# Final_3.net
KiCad netlist of a schematic drawn in EAGLE
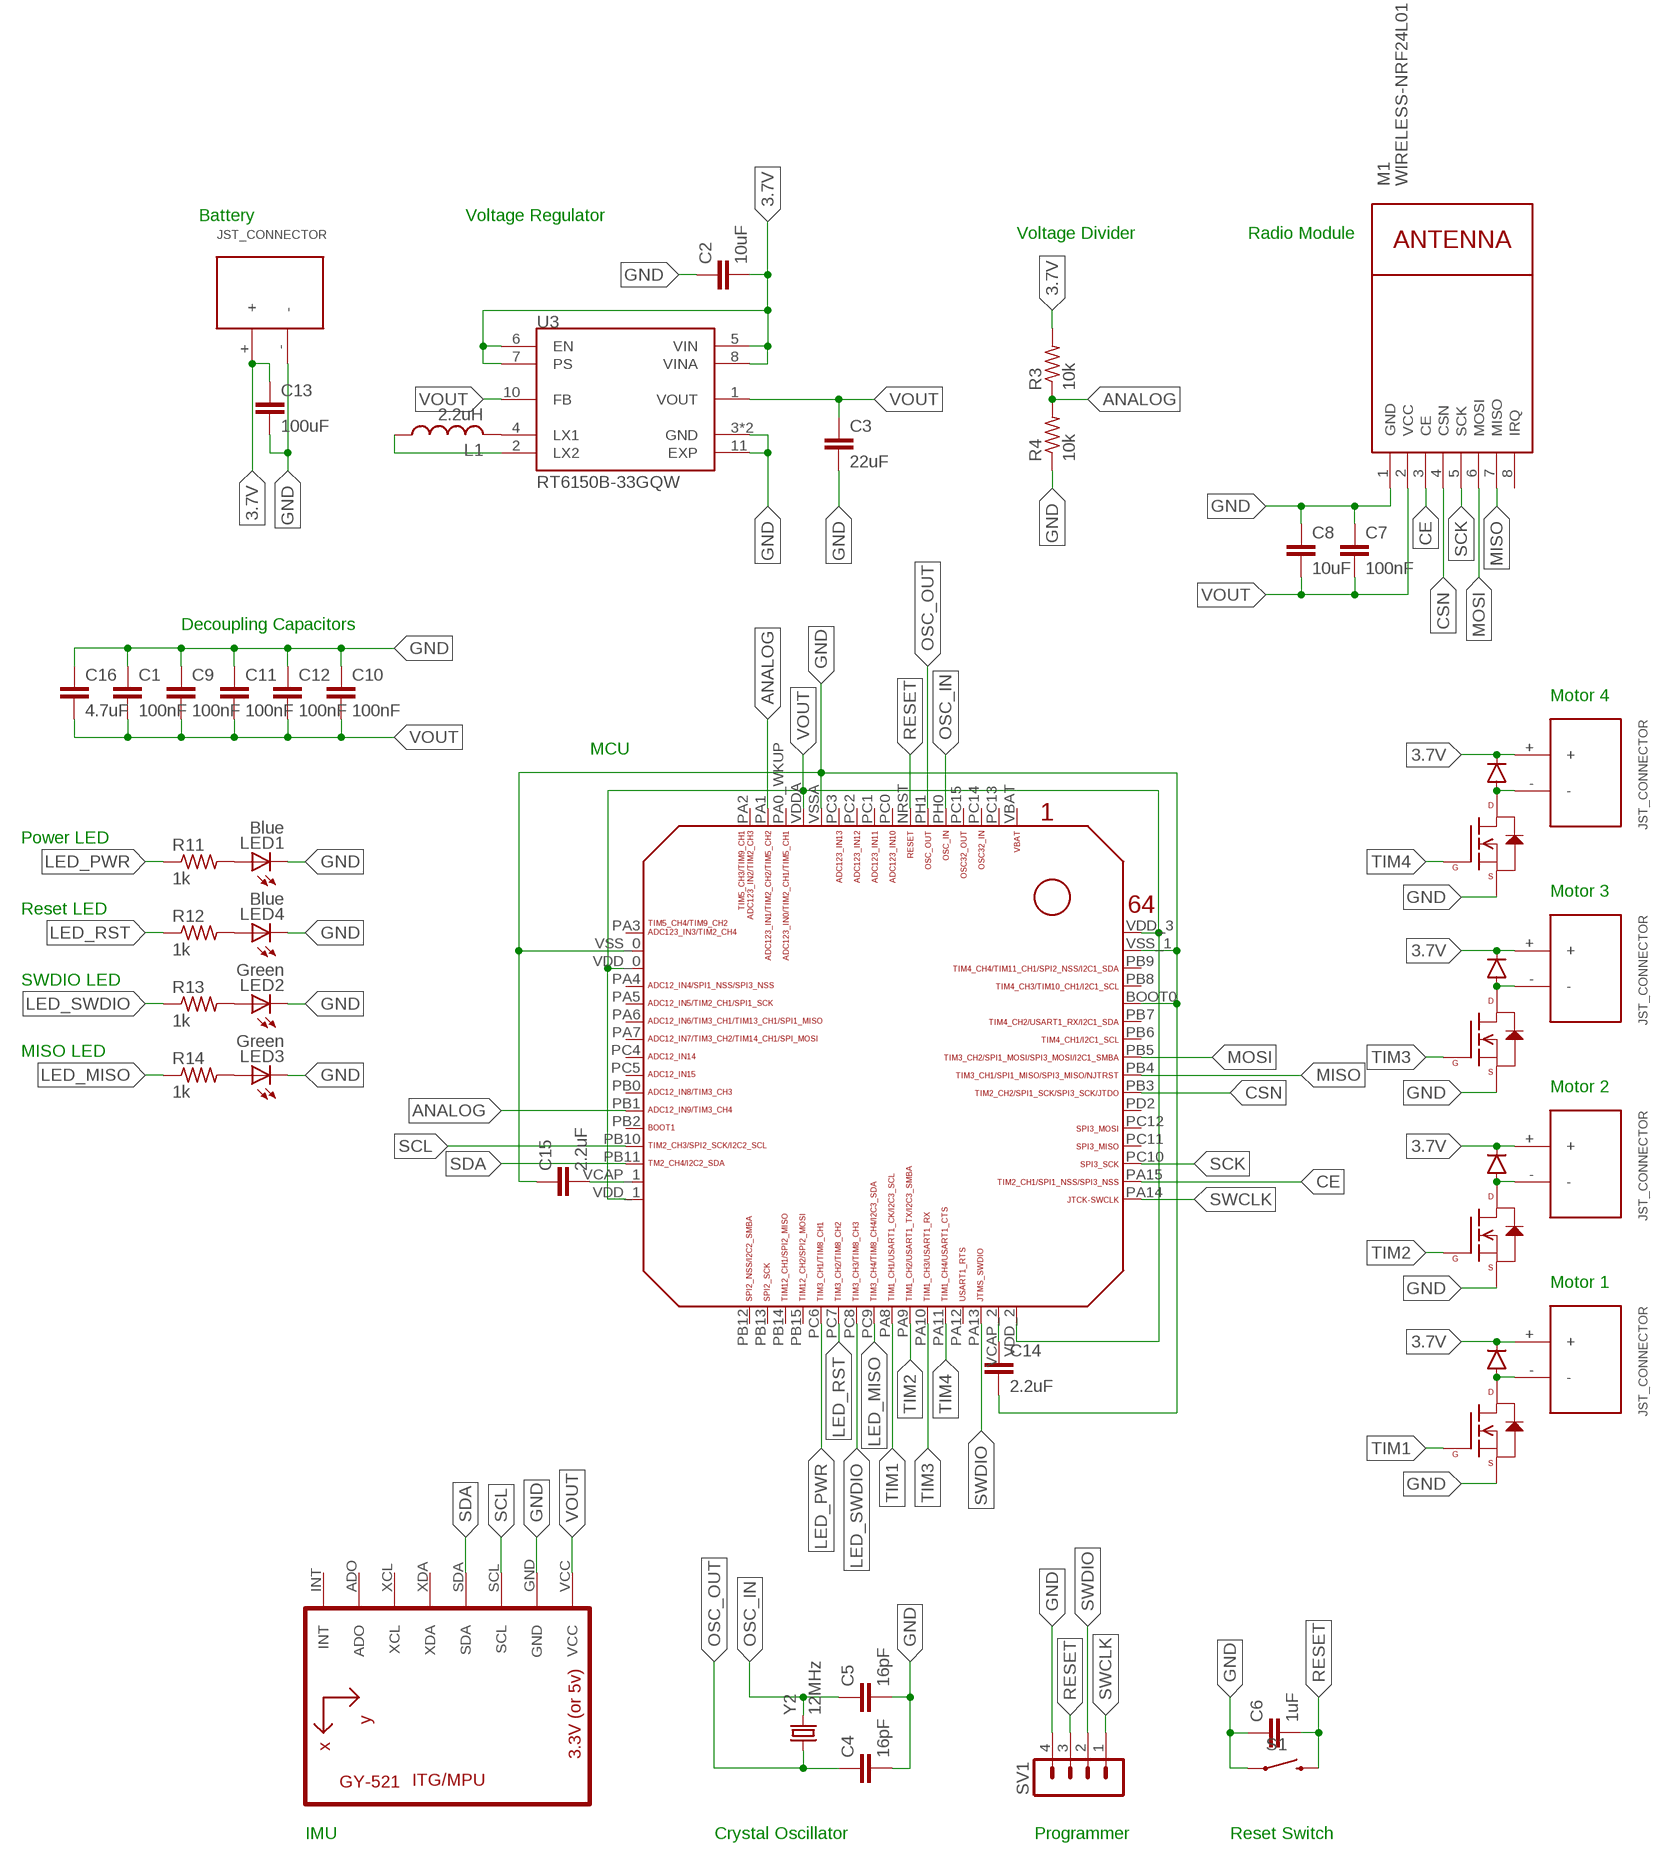
[diagram p0: schematic, sheet 1]

(export (version "E")
  (design (tool "Eeschema 10.0.6"))
  (components
    (comp (ref "C1")
      (value "100nF")
      (footprint "eagle-import:C0603")
      (libsource (lib "eagle-import") (part "rcl_334_C-EUC0603"))
    )
    (comp (ref "C2")
      (value "10uF")
      (footprint "eagle-import:C0603")
      (libsource (lib "eagle-import") (part "rcl_334_C-EUC0603"))
    )
    (comp (ref "C3")
      (value "22uF")
      (footprint "eagle-import:C0603")
      (libsource (lib "eagle-import") (part "rcl_334_C-EUC0603"))
    )
    (comp (ref "C4")
      (value "16pF")
      (footprint "eagle-import:C0603")
      (libsource (lib "eagle-import") (part "rcl_334_C-EUC0603"))
    )
    (comp (ref "C5")
      (value "16pF")
      (footprint "eagle-import:C0603")
      (libsource (lib "eagle-import") (part "rcl_334_C-EUC0603"))
    )
    (comp (ref "C6")
      (value "1uF")
      (footprint "eagle-import:C0603")
      (libsource (lib "eagle-import") (part "rcl_334_C-EUC0603"))
    )
    (comp (ref "C7")
      (value "100nF")
      (footprint "eagle-import:C0603")
      (libsource (lib "eagle-import") (part "rcl_334_C-EUC0603"))
    )
    (comp (ref "C8")
      (value "10uF")
      (footprint "eagle-import:C0603")
      (libsource (lib "eagle-import") (part "rcl_334_C-EUC0603"))
    )
    (comp (ref "C9")
      (value "100nF")
      (footprint "eagle-import:C0603")
      (libsource (lib "eagle-import") (part "rcl_334_C-EUC0603"))
    )
    (comp (ref "C10")
      (value "100nF")
      (footprint "eagle-import:C0603")
      (libsource (lib "eagle-import") (part "rcl_334_C-EUC0603"))
    )
    (comp (ref "C11")
      (value "100nF")
      (footprint "eagle-import:C0603")
      (libsource (lib "eagle-import") (part "rcl_334_C-EUC0603"))
    )
    (comp (ref "C12")
      (value "100nF")
      (footprint "eagle-import:C0603")
      (libsource (lib "eagle-import") (part "rcl_334_C-EUC0603"))
    )
    (comp (ref "C13")
      (value "100uF")
      (footprint "eagle-import:C1206")
      (libsource (lib "eagle-import") (part "rcl_334_C-EUC1206"))
    )
    (comp (ref "C14")
      (value "2.2uF")
      (footprint "eagle-import:C0603")
      (libsource (lib "eagle-import") (part "C-EUC0603"))
    )
    (comp (ref "C15")
      (value "2.2uF")
      (footprint "eagle-import:C0603")
      (libsource (lib "eagle-import") (part "C-EUC0603"))
    )
    (comp (ref "C16")
      (value "4.7uF")
      (footprint "eagle-import:C0603")
      (libsource (lib "eagle-import") (part "rcl_334_C-EUC0603"))
    )
    (comp (ref "L1")
      (value "2.2uH")
      (footprint "eagle-import:L0603")
      (libsource (lib "eagle-import") (part "L-USL0603"))
    )
    (comp (ref "LED1")
      (value "Blue")
      (footprint "eagle-import:CHIP-LED0603")
      (libsource (lib "eagle-import") (part "LEDCHIP-LED0603"))
    )
    (comp (ref "LED2")
      (value "Green")
      (footprint "eagle-import:CHIP-LED0603")
      (libsource (lib "eagle-import") (part "LEDCHIP-LED0603"))
    )
    (comp (ref "LED3")
      (value "Green")
      (footprint "eagle-import:CHIP-LED0603")
      (libsource (lib "eagle-import") (part "LEDCHIP-LED0603"))
    )
    (comp (ref "LED4")
      (value "Blue")
      (footprint "eagle-import:CHIP-LED0603")
      (libsource (lib "eagle-import") (part "LEDCHIP-LED0603"))
    )
    (comp (ref "M1")
      (value "WIRELESS-NRF24L01")
      (footprint "eagle-import:WIRELESS-NRF24L01")
      (libsource (lib "eagle-import") (part "WIRELESS-NRF24L01"))
    )
    (comp (ref "R3")
      (value "10k")
      (footprint "eagle-import:R0603")
      (libsource (lib "eagle-import") (part "R-US_R0603"))
    )
    (comp (ref "R4")
      (value "10k")
      (footprint "eagle-import:R0603")
      (libsource (lib "eagle-import") (part "R-US_R0603"))
    )
    (comp (ref "R11")
      (value "1k")
      (footprint "eagle-import:R0603")
      (libsource (lib "eagle-import") (part "R-US_R0603"))
    )
    (comp (ref "R12")
      (value "1k")
      (footprint "eagle-import:R0603")
      (libsource (lib "eagle-import") (part "R-US_R0603"))
    )
    (comp (ref "R13")
      (value "1k")
      (footprint "eagle-import:R0603")
      (libsource (lib "eagle-import") (part "R-US_R0603"))
    )
    (comp (ref "R14")
      (value "1k")
      (footprint "eagle-import:R0603")
      (libsource (lib "eagle-import") (part "R-US_R0603"))
    )
    (comp (ref "S1")
      (value "SWITCH-MOMENTARY-2SMD")
      (footprint "eagle-import:TACTILE-SWITCH-SMD")
      (libsource (lib "eagle-import") (part "SWITCH-MOMENTARY-2SMD"))
    )
    (comp (ref "SV1")
      (value "MA04-1")
      (footprint "eagle-import:MA04-1")
      (libsource (lib "eagle-import") (part "MA04-1"))
    )
    (comp (ref "U$1")
      (value "STM32F405/415_LQFP64")
      (footprint "eagle-import:STM32F405_415_LQFP64")
      (libsource (lib "eagle-import") (part "STM32F405/415_LQFP64"))
    )
    (comp (ref "U$2")
      (value "JST_CONNECTOR_FEMALE")
      (footprint "eagle-import:JST_CONNECTOR_FEMALE")
      (libsource (lib "eagle-import") (part "JST_CONNECTOR_FEMALE"))
    )
    (comp (ref "U$3")
      (value "JST_CONNECTOR_FEMALE")
      (footprint "eagle-import:JST_CONNECTOR_FEMALE")
      (libsource (lib "eagle-import") (part "JST_CONNECTOR_FEMALE"))
    )
    (comp (ref "U$4")
      (value "JST_CONNECTOR_FEMALE")
      (footprint "eagle-import:JST_CONNECTOR_FEMALE")
      (libsource (lib "eagle-import") (part "JST_CONNECTOR_FEMALE"))
    )
    (comp (ref "U$5")
      (value "JST_CONNECTOR_FEMALE")
      (footprint "eagle-import:JST_CONNECTOR_FEMALE")
      (libsource (lib "eagle-import") (part "JST_CONNECTOR_FEMALE"))
    )
    (comp (ref "U$6")
      (value "JST_CONNECTOR_FEMALE")
      (footprint "eagle-import:JST_CONNECTOR_FEMALE")
      (libsource (lib "eagle-import") (part "JST_CONNECTOR_FEMALE"))
    )
    (comp (ref "U$7")
      (value "N-CHANNEL-MOSFET-IRLML6244TRPBF")
      (footprint "eagle-import:SOT23-3")
      (libsource (lib "eagle-import") (part "N-CHANNEL-MOSFET-IRLML6244TRPBF"))
    )
    (comp (ref "U$8")
      (value "N-CHANNEL-MOSFET-IRLML6244TRPBF")
      (footprint "eagle-import:SOT23-3")
      (libsource (lib "eagle-import") (part "N-CHANNEL-MOSFET-IRLML6244TRPBF"))
    )
    (comp (ref "U$9")
      (value "N-CHANNEL-MOSFET-IRLML6244TRPBF")
      (footprint "eagle-import:SOT23-3")
      (libsource (lib "eagle-import") (part "N-CHANNEL-MOSFET-IRLML6244TRPBF"))
    )
    (comp (ref "U$10")
      (value "N-CHANNEL-MOSFET-IRLML6244TRPBF")
      (footprint "eagle-import:SOT23-3")
      (libsource (lib "eagle-import") (part "N-CHANNEL-MOSFET-IRLML6244TRPBF"))
    )
    (comp (ref "U$11")
      (value "DB2W40300L")
      (footprint "eagle-import:MINI2-F3-B")
      (libsource (lib "eagle-import") (part "DB2W40300L"))
    )
    (comp (ref "U$12")
      (value "DB2W40300L")
      (footprint "eagle-import:MINI2-F3-B")
      (libsource (lib "eagle-import") (part "DB2W40300L"))
    )
    (comp (ref "U$13")
      (value "DB2W40300L")
      (footprint "eagle-import:MINI2-F3-B")
      (libsource (lib "eagle-import") (part "DB2W40300L"))
    )
    (comp (ref "U$14")
      (value "DB2W40300L")
      (footprint "eagle-import:MINI2-F3-B")
      (libsource (lib "eagle-import") (part "DB2W40300L"))
    )
    (comp (ref "U2")
      (value "GY-521MPU6050")
      (footprint "eagle-import:GY-521")
      (libsource (lib "eagle-import") (part "GY-521MPU6050"))
    )
    (comp (ref "U3")
      (value "RT6150B-33GQW")
      (footprint "eagle-import:SON50P250X250X80-11N")
      (fields (field (name "DIGI-KEY_PART_NUMBER") "RT6150B-33GQWCT-ND") (field (name "MF") "Richtek USA"))
      (libsource (lib "eagle-import") (part "RT6150B-33GQW"))
    )
    (comp (ref "Y2")
      (value "12MHz")
      (footprint "eagle-import:HC49UP")
      (libsource (lib "eagle-import") (part "CRYSTALSMD"))
    )
  )
  (nets
    (net (code "1") (name "3.7V") (class "Default")
      (node (ref "C13") (pin "1") (pinfunction "1_1") (pintype "passive"))
      (node (ref "C2") (pin "2") (pinfunction "2_2") (pintype "passive"))
      (node (ref "R3") (pin "2") (pinfunction "2_2") (pintype "passive"))
      (node (ref "U$11") (pin "NEG") (pinfunction "GPIN_NEG") (pintype "passive"))
      (node (ref "U$12") (pin "NEG") (pinfunction "GPIN_NEG") (pintype "passive"))
      (node (ref "U$13") (pin "NEG") (pinfunction "GPIN_NEG") (pintype "passive"))
      (node (ref "U$14") (pin "NEG") (pinfunction "GPIN_NEG") (pintype "passive"))
      (node (ref "U$2") (pin "+") (pinfunction "+_+") (pintype "bidirectional"))
      (node (ref "U$3") (pin "+") (pinfunction "+_+") (pintype "bidirectional"))
      (node (ref "U$4") (pin "+") (pinfunction "+_+") (pintype "bidirectional"))
      (node (ref "U$5") (pin "+") (pinfunction "+_+") (pintype "bidirectional"))
      (node (ref "U$6") (pin "+") (pinfunction "+_+") (pintype "bidirectional"))
      (node (ref "U3") (pin "5") (pinfunction "VIN_5") (pintype "power_in"))
      (node (ref "U3") (pin "6") (pinfunction "EN_6") (pintype "input"))
      (node (ref "U3") (pin "7") (pinfunction "PS_7") (pintype "input"))
      (node (ref "U3") (pin "8") (pinfunction "VINA_8") (pintype "power_in"))
    )
    (net (code "2") (name "ANALOG") (class "Default")
      (node (ref "R3") (pin "1") (pinfunction "1_1") (pintype "passive"))
      (node (ref "R4") (pin "2") (pinfunction "2_2") (pintype "passive"))
      (node (ref "U$1") (pin "PA1") (pinfunction "PA1_PA1") (pintype "bidirectional"))
      (node (ref "U$1") (pin "PB1") (pinfunction "PB1_PB1") (pintype "bidirectional"))
    )
    (net (code "3") (name "CE") (class "Default")
      (node (ref "M1") (pin "3") (pinfunction "CE_3") (pintype "bidirectional"))
      (node (ref "U$1") (pin "PA15") (pinfunction "PA15_PA15") (pintype "bidirectional"))
    )
    (net (code "4") (name "CSN") (class "Default")
      (node (ref "M1") (pin "4") (pinfunction "CSN_4") (pintype "bidirectional"))
      (node (ref "U$1") (pin "PB3") (pinfunction "PB3_PB3") (pintype "bidirectional"))
    )
    (net (code "5") (name "GND") (class "Default")
      (node (ref "C1") (pin "1") (pinfunction "1_1") (pintype "passive"))
      (node (ref "C10") (pin "1") (pinfunction "1_1") (pintype "passive"))
      (node (ref "C11") (pin "1") (pinfunction "1_1") (pintype "passive"))
      (node (ref "C12") (pin "1") (pinfunction "1_1") (pintype "passive"))
      (node (ref "C13") (pin "2") (pinfunction "2_2") (pintype "passive"))
      (node (ref "C14") (pin "2") (pinfunction "2_2") (pintype "passive"))
      (node (ref "C15") (pin "1") (pinfunction "1_1") (pintype "passive"))
      (node (ref "C16") (pin "1") (pinfunction "1_1") (pintype "passive"))
      (node (ref "C2") (pin "1") (pinfunction "1_1") (pintype "passive"))
      (node (ref "C3") (pin "2") (pinfunction "2_2") (pintype "passive"))
      (node (ref "C4") (pin "2") (pinfunction "2_2") (pintype "passive"))
      (node (ref "C5") (pin "2") (pinfunction "2_2") (pintype "passive"))
      (node (ref "C6") (pin "1") (pinfunction "1_1") (pintype "passive"))
      (node (ref "C7") (pin "1") (pinfunction "1_1") (pintype "passive"))
      (node (ref "C8") (pin "1") (pinfunction "1_1") (pintype "passive"))
      (node (ref "C9") (pin "1") (pinfunction "1_1") (pintype "passive"))
      (node (ref "LED1") (pin "C") (pinfunction "C_C") (pintype "passive"))
      (node (ref "LED2") (pin "C") (pinfunction "C_C") (pintype "passive"))
      (node (ref "LED3") (pin "C") (pinfunction "C_C") (pintype "passive"))
      (node (ref "LED4") (pin "C") (pinfunction "C_C") (pintype "passive"))
      (node (ref "M1") (pin "1") (pinfunction "GND_1") (pintype "power_in"))
      (node (ref "R4") (pin "1") (pinfunction "1_1") (pintype "passive"))
      (node (ref "S1") (pin "1") (pinfunction "1_1") (pintype "passive"))
      (node (ref "SV1") (pin "4") (pinfunction "4_4") (pintype "passive"))
      (node (ref "U$1") (pin "BOOT0") (pinfunction "BOOT0_BOOT0") (pintype "bidirectional"))
      (node (ref "U$1") (pin "VSSA") (pinfunction "VSSA_VSSA") (pintype "bidirectional"))
      (node (ref "U$1") (pin "VSS_0") (pinfunction "VSS_0_VSS_0") (pintype "bidirectional"))
      (node (ref "U$1") (pin "VSS_1") (pinfunction "VSS_1_VSS_1") (pintype "bidirectional"))
      (node (ref "U$10") (pin "2") (pinfunction "S_2") (pintype "passive"))
      (node (ref "U$2") (pin "-") (pinfunction "-_-") (pintype "bidirectional"))
      (node (ref "U$7") (pin "2") (pinfunction "S_2") (pintype "passive"))
      (node (ref "U$8") (pin "2") (pinfunction "S_2") (pintype "passive"))
      (node (ref "U$9") (pin "2") (pinfunction "S_2") (pintype "passive"))
      (node (ref "U2") (pin "GND") (pinfunction "GND_GND") (pintype "bidirectional"))
      (node (ref "U3") (pin "11") (pinfunction "EXP_11") (pintype "passive"))
      (node (ref "U3") (pin "3") (pinfunction "GND_3") (pintype "power_in"))
      (node (ref "U3") (pin "9") (pinfunction "GND_9") (pintype "power_in"))
    )
    (net (code "6") (name "LED_MISO") (class "Default")
      (node (ref "R14") (pin "1") (pinfunction "1_1") (pintype "passive"))
      (node (ref "U$1") (pin "PC9") (pinfunction "PC9_PC9") (pintype "bidirectional"))
    )
    (net (code "7") (name "LED_PWR") (class "Default")
      (node (ref "R11") (pin "1") (pinfunction "1_1") (pintype "passive"))
      (node (ref "U$1") (pin "PC6") (pinfunction "PC6_PC6") (pintype "bidirectional"))
    )
    (net (code "8") (name "LED_RST") (class "Default")
      (node (ref "R12") (pin "1") (pinfunction "1_1") (pintype "passive"))
      (node (ref "U$1") (pin "PC7") (pinfunction "PC7_PC7") (pintype "bidirectional"))
    )
    (net (code "9") (name "LED_SWDIO") (class "Default")
      (node (ref "R13") (pin "1") (pinfunction "1_1") (pintype "passive"))
      (node (ref "U$1") (pin "PC8") (pinfunction "PC8_PC8") (pintype "bidirectional"))
    )
    (net (code "10") (name "MISO") (class "Default")
      (node (ref "M1") (pin "7") (pinfunction "MISO_7") (pintype "bidirectional"))
      (node (ref "U$1") (pin "PB4") (pinfunction "PB4_PB4") (pintype "bidirectional"))
    )
    (net (code "11") (name "MOSI") (class "Default")
      (node (ref "M1") (pin "6") (pinfunction "MOSI_6") (pintype "bidirectional"))
      (node (ref "U$1") (pin "PB5") (pinfunction "PB5_PB5") (pintype "bidirectional"))
    )
    (net (code "12") (name "Net-(C14-Pad1)") (class "Default")
      (node (ref "C14") (pin "1") (pinfunction "1_1") (pintype "passive"))
      (node (ref "U$1") (pin "VCAP_2") (pinfunction "VCAP_2_VCAP_2") (pintype "bidirectional"))
    )
    (net (code "13") (name "Net-(C15-Pad2)") (class "Default")
      (node (ref "C15") (pin "2") (pinfunction "2_2") (pintype "passive"))
      (node (ref "U$1") (pin "VCAP_1") (pinfunction "VCAP_1_VCAP_1") (pintype "bidirectional"))
    )
    (net (code "14") (name "Net-(LED1-PadA)") (class "Default")
      (node (ref "LED1") (pin "A") (pinfunction "A_A") (pintype "passive"))
      (node (ref "R11") (pin "2") (pinfunction "2_2") (pintype "passive"))
    )
    (net (code "15") (name "Net-(LED2-PadA)") (class "Default")
      (node (ref "LED2") (pin "A") (pinfunction "A_A") (pintype "passive"))
      (node (ref "R13") (pin "2") (pinfunction "2_2") (pintype "passive"))
    )
    (net (code "16") (name "Net-(LED3-PadA)") (class "Default")
      (node (ref "LED3") (pin "A") (pinfunction "A_A") (pintype "passive"))
      (node (ref "R14") (pin "2") (pinfunction "2_2") (pintype "passive"))
    )
    (net (code "17") (name "Net-(LED4-PadA)") (class "Default")
      (node (ref "LED4") (pin "A") (pinfunction "A_A") (pintype "passive"))
      (node (ref "R12") (pin "2") (pinfunction "2_2") (pintype "passive"))
    )
    (net (code "18") (name "Net-(U$10-D)") (class "Default")
      (node (ref "U$10") (pin "3") (pinfunction "D_3") (pintype "passive"))
      (node (ref "U$14") (pin "POS") (pinfunction "PPIN_POS") (pintype "passive"))
      (node (ref "U$6") (pin "-") (pinfunction "-_-") (pintype "bidirectional"))
    )
    (net (code "19") (name "Net-(U$11-PPIN)") (class "Default")
      (node (ref "U$11") (pin "POS") (pinfunction "PPIN_POS") (pintype "passive"))
      (node (ref "U$3") (pin "-") (pinfunction "-_-") (pintype "bidirectional"))
      (node (ref "U$9") (pin "3") (pinfunction "D_3") (pintype "passive"))
    )
    (net (code "20") (name "Net-(U$12-PPIN)") (class "Default")
      (node (ref "U$12") (pin "POS") (pinfunction "PPIN_POS") (pintype "passive"))
      (node (ref "U$5") (pin "-") (pinfunction "-_-") (pintype "bidirectional"))
      (node (ref "U$8") (pin "3") (pinfunction "D_3") (pintype "passive"))
    )
    (net (code "21") (name "Net-(U$13-PPIN)") (class "Default")
      (node (ref "U$13") (pin "POS") (pinfunction "PPIN_POS") (pintype "passive"))
      (node (ref "U$4") (pin "-") (pinfunction "-_-") (pintype "bidirectional"))
      (node (ref "U$7") (pin "3") (pinfunction "D_3") (pintype "passive"))
    )
    (net (code "22") (name "Net-(U3-LX1)") (class "Default")
      (node (ref "L1") (pin "2") (pinfunction "2_2") (pintype "passive"))
      (node (ref "U3") (pin "4") (pinfunction "LX1_4") (pintype "passive"))
    )
    (net (code "23") (name "Net-(U3-LX2)") (class "Default")
      (node (ref "L1") (pin "1") (pinfunction "1_1") (pintype "passive"))
      (node (ref "U3") (pin "2") (pinfunction "LX2_2") (pintype "passive"))
    )
    (net (code "24") (name "OSC_IN") (class "Default")
      (node (ref "C5") (pin "1") (pinfunction "1_1") (pintype "passive"))
      (node (ref "U$1") (pin "PH0") (pinfunction "PH0_PH0") (pintype "bidirectional"))
      (node (ref "Y2") (pin "2") (pinfunction "2_2") (pintype "passive"))
    )
    (net (code "25") (name "OSC_OUT") (class "Default")
      (node (ref "C4") (pin "1") (pinfunction "1_1") (pintype "passive"))
      (node (ref "U$1") (pin "PH1") (pinfunction "PH1_PH1") (pintype "bidirectional"))
      (node (ref "Y2") (pin "1") (pinfunction "1_1") (pintype "passive"))
    )
    (net (code "26") (name "RESET") (class "Default")
      (node (ref "C6") (pin "2") (pinfunction "2_2") (pintype "passive"))
      (node (ref "S1") (pin "3") (pinfunction "2_3") (pintype "passive"))
      (node (ref "SV1") (pin "3") (pinfunction "3_3") (pintype "passive"))
      (node (ref "U$1") (pin "NRST") (pinfunction "NRST_NRST") (pintype "bidirectional"))
    )
    (net (code "27") (name "SCK") (class "Default")
      (node (ref "M1") (pin "5") (pinfunction "SCK_5") (pintype "bidirectional"))
      (node (ref "U$1") (pin "PC10") (pinfunction "PC10_PC10") (pintype "bidirectional"))
    )
    (net (code "28") (name "SCL") (class "Default")
      (node (ref "U$1") (pin "PB10") (pinfunction "PB10_PB10") (pintype "bidirectional"))
      (node (ref "U2") (pin "SCL") (pinfunction "SCL_SCL") (pintype "bidirectional"))
    )
    (net (code "29") (name "SDA") (class "Default")
      (node (ref "U$1") (pin "PB11") (pinfunction "PB11_PB11") (pintype "bidirectional"))
      (node (ref "U2") (pin "SDA") (pinfunction "SDA_SDA") (pintype "bidirectional"))
    )
    (net (code "30") (name "SWCLK") (class "Default")
      (node (ref "SV1") (pin "1") (pinfunction "1_1") (pintype "passive"))
      (node (ref "U$1") (pin "PA14") (pinfunction "PA14_PA14") (pintype "bidirectional"))
    )
    (net (code "31") (name "SWDIO") (class "Default")
      (node (ref "SV1") (pin "2") (pinfunction "2_2") (pintype "passive"))
      (node (ref "U$1") (pin "PA13") (pinfunction "PA13_PA13") (pintype "bidirectional"))
    )
    (net (code "32") (name "TIM1") (class "Default")
      (node (ref "U$1") (pin "PA8") (pinfunction "PA8_PA8") (pintype "bidirectional"))
      (node (ref "U$10") (pin "1") (pinfunction "G_1") (pintype "passive"))
    )
    (net (code "33") (name "TIM2") (class "Default")
      (node (ref "U$1") (pin "PA9") (pinfunction "PA9_PA9") (pintype "bidirectional"))
      (node (ref "U$8") (pin "1") (pinfunction "G_1") (pintype "passive"))
    )
    (net (code "34") (name "TIM3") (class "Default")
      (node (ref "U$1") (pin "PA10") (pinfunction "PA10_PA10") (pintype "bidirectional"))
      (node (ref "U$7") (pin "1") (pinfunction "G_1") (pintype "passive"))
    )
    (net (code "35") (name "TIM4") (class "Default")
      (node (ref "U$1") (pin "PA11") (pinfunction "PA11_PA11") (pintype "bidirectional"))
      (node (ref "U$9") (pin "1") (pinfunction "G_1") (pintype "passive"))
    )
    (net (code "36") (name "VOUT") (class "Default")
      (node (ref "C1") (pin "2") (pinfunction "2_2") (pintype "passive"))
      (node (ref "C10") (pin "2") (pinfunction "2_2") (pintype "passive"))
      (node (ref "C11") (pin "2") (pinfunction "2_2") (pintype "passive"))
      (node (ref "C12") (pin "2") (pinfunction "2_2") (pintype "passive"))
      (node (ref "C16") (pin "2") (pinfunction "2_2") (pintype "passive"))
      (node (ref "C3") (pin "1") (pinfunction "1_1") (pintype "passive"))
      (node (ref "C7") (pin "2") (pinfunction "2_2") (pintype "passive"))
      (node (ref "C8") (pin "2") (pinfunction "2_2") (pintype "passive"))
      (node (ref "C9") (pin "2") (pinfunction "2_2") (pintype "passive"))
      (node (ref "M1") (pin "2") (pinfunction "VCC_2") (pintype "power_in"))
      (node (ref "U$1") (pin "VDDA") (pinfunction "VDDA_VDDA") (pintype "bidirectional"))
      (node (ref "U$1") (pin "VDD_0") (pinfunction "VDD_0_VDD_0") (pintype "bidirectional"))
      (node (ref "U$1") (pin "VDD_1") (pinfunction "VDD_1_VDD_1") (pintype "bidirectional"))
      (node (ref "U$1") (pin "VDD_2") (pinfunction "VDD_2_VDD_2") (pintype "bidirectional"))
      (node (ref "U$1") (pin "VDD_3") (pinfunction "VDD_3_VDD_3") (pintype "bidirectional"))
      (node (ref "U2") (pin "VCC") (pinfunction "VCC_VCC") (pintype "bidirectional"))
      (node (ref "U3") (pin "1") (pinfunction "VOUT_1") (pintype "output"))
      (node (ref "U3") (pin "10") (pinfunction "FB_10") (pintype "input"))
    )
    (net (code "37") (name "unconnected-(M1-IRQ-Pad8)") (class "Default")
      (node (ref "M1") (pin "8") (pinfunction "IRQ_8") (pintype "bidirectional"))
    )
    (net (code "38") (name "unconnected-(U$1-PA0_AKUP-PadPA0_WKUP)") (class "Default")
      (node (ref "U$1") (pin "PA0_WKUP") (pinfunction "PA0_AKUP_PA0_WKUP") (pintype "bidirectional"))
    )
    (net (code "39") (name "unconnected-(U$1-PadPA2)") (class "Default")
      (node (ref "U$1") (pin "PA2") (pinfunction "PA2_PA2") (pintype "bidirectional"))
    )
    (net (code "40") (name "unconnected-(U$1-PadPA3)") (class "Default")
      (node (ref "U$1") (pin "PA3") (pinfunction "PA3_PA3") (pintype "bidirectional"))
    )
    (net (code "41") (name "unconnected-(U$1-PadPA4)") (class "Default")
      (node (ref "U$1") (pin "PA4") (pinfunction "PA4_PA4") (pintype "bidirectional"))
    )
    (net (code "42") (name "unconnected-(U$1-PadPA5)") (class "Default")
      (node (ref "U$1") (pin "PA5") (pinfunction "PA5_PA5") (pintype "bidirectional"))
    )
    (net (code "43") (name "unconnected-(U$1-PadPA6)") (class "Default")
      (node (ref "U$1") (pin "PA6") (pinfunction "PA6_PA6") (pintype "bidirectional"))
    )
    (net (code "44") (name "unconnected-(U$1-PadPA7)") (class "Default")
      (node (ref "U$1") (pin "PA7") (pinfunction "PA7_PA7") (pintype "bidirectional"))
    )
    (net (code "45") (name "unconnected-(U$1-PadPA12)") (class "Default")
      (node (ref "U$1") (pin "PA12") (pinfunction "PA12_PA12") (pintype "bidirectional"))
    )
    (net (code "46") (name "unconnected-(U$1-PadPB0)") (class "Default")
      (node (ref "U$1") (pin "PB0") (pinfunction "PB0_PB0") (pintype "bidirectional"))
    )
    (net (code "47") (name "unconnected-(U$1-PadPB2)") (class "Default")
      (node (ref "U$1") (pin "PB2") (pinfunction "PB2_PB2") (pintype "bidirectional"))
    )
    (net (code "48") (name "unconnected-(U$1-PadPB6)") (class "Default")
      (node (ref "U$1") (pin "PB6") (pinfunction "PB6_PB6") (pintype "bidirectional"))
    )
    (net (code "49") (name "unconnected-(U$1-PadPB7)") (class "Default")
      (node (ref "U$1") (pin "PB7") (pinfunction "PB7_PB7") (pintype "bidirectional"))
    )
    (net (code "50") (name "unconnected-(U$1-PadPB8)") (class "Default")
      (node (ref "U$1") (pin "PB8") (pinfunction "PB8_PB8") (pintype "bidirectional"))
    )
    (net (code "51") (name "unconnected-(U$1-PadPB9)") (class "Default")
      (node (ref "U$1") (pin "PB9") (pinfunction "PB9_PB9") (pintype "bidirectional"))
    )
    (net (code "52") (name "unconnected-(U$1-PadPB12)") (class "Default")
      (node (ref "U$1") (pin "PB12") (pinfunction "PB12_PB12") (pintype "bidirectional"))
    )
    (net (code "53") (name "unconnected-(U$1-PadPB13)") (class "Default")
      (node (ref "U$1") (pin "PB13") (pinfunction "PB13_PB13") (pintype "bidirectional"))
    )
    (net (code "54") (name "unconnected-(U$1-PadPB14)") (class "Default")
      (node (ref "U$1") (pin "PB14") (pinfunction "PB14_PB14") (pintype "bidirectional"))
    )
    (net (code "55") (name "unconnected-(U$1-PadPB15)") (class "Default")
      (node (ref "U$1") (pin "PB15") (pinfunction "PB15_PB15") (pintype "bidirectional"))
    )
    (net (code "56") (name "unconnected-(U$1-PadPC0)") (class "Default")
      (node (ref "U$1") (pin "PC0") (pinfunction "PC0_PC0") (pintype "bidirectional"))
    )
    (net (code "57") (name "unconnected-(U$1-PadPC1)") (class "Default")
      (node (ref "U$1") (pin "PC1") (pinfunction "PC1_PC1") (pintype "bidirectional"))
    )
    (net (code "58") (name "unconnected-(U$1-PadPC2)") (class "Default")
      (node (ref "U$1") (pin "PC2") (pinfunction "PC2_PC2") (pintype "bidirectional"))
    )
    (net (code "59") (name "unconnected-(U$1-PadPC3)") (class "Default")
      (node (ref "U$1") (pin "PC3") (pinfunction "PC3_PC3") (pintype "bidirectional"))
    )
    (net (code "60") (name "unconnected-(U$1-PadPC4)") (class "Default")
      (node (ref "U$1") (pin "PC4") (pinfunction "PC4_PC4") (pintype "bidirectional"))
    )
    (net (code "61") (name "unconnected-(U$1-PadPC5)") (class "Default")
      (node (ref "U$1") (pin "PC5") (pinfunction "PC5_PC5") (pintype "bidirectional"))
    )
    (net (code "62") (name "unconnected-(U$1-PadPC11)") (class "Default")
      (node (ref "U$1") (pin "PC11") (pinfunction "PC11_PC11") (pintype "bidirectional"))
    )
    (net (code "63") (name "unconnected-(U$1-PadPC12)") (class "Default")
      (node (ref "U$1") (pin "PC12") (pinfunction "PC12_PC12") (pintype "bidirectional"))
    )
    (net (code "64") (name "unconnected-(U$1-PadPC13)") (class "Default")
      (node (ref "U$1") (pin "PC13") (pinfunction "PC13_PC13") (pintype "bidirectional"))
    )
    (net (code "65") (name "unconnected-(U$1-PadPC14)") (class "Default")
      (node (ref "U$1") (pin "PC14") (pinfunction "PC14_PC14") (pintype "bidirectional"))
    )
    (net (code "66") (name "unconnected-(U$1-PadPC15)") (class "Default")
      (node (ref "U$1") (pin "PC15") (pinfunction "PC15_PC15") (pintype "bidirectional"))
    )
    (net (code "67") (name "unconnected-(U$1-PadPD2)") (class "Default")
      (node (ref "U$1") (pin "PD2") (pinfunction "PD2_PD2") (pintype "bidirectional"))
    )
    (net (code "68") (name "unconnected-(U$1-PadVBAT)") (class "Default")
      (node (ref "U$1") (pin "VBAT") (pinfunction "VBAT_VBAT") (pintype "bidirectional"))
    )
    (net (code "69") (name "unconnected-(U2-PadADO)") (class "Default")
      (node (ref "U2") (pin "ADO") (pinfunction "ADO_ADO") (pintype "bidirectional"))
    )
    (net (code "70") (name "unconnected-(U2-PadINT)") (class "Default")
      (node (ref "U2") (pin "INT") (pinfunction "INT_INT") (pintype "bidirectional"))
    )
    (net (code "71") (name "unconnected-(U2-PadXCL)") (class "Default")
      (node (ref "U2") (pin "XCL") (pinfunction "XCL_XCL") (pintype "bidirectional"))
    )
    (net (code "72") (name "unconnected-(U2-PadXDA)") (class "Default")
      (node (ref "U2") (pin "XDA") (pinfunction "XDA_XDA") (pintype "bidirectional"))
    )
  )
)
